# RadioCommunication.net
KiCad netlist of a schematic drawn in Altium Designer
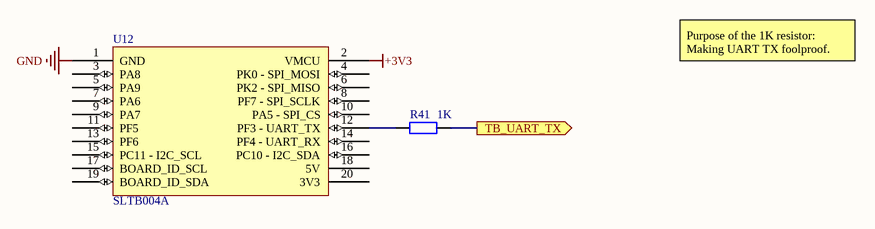
[diagram p0: RadioCommunication.SchDoc]

(export (version "E")
  (design (tool "Eeschema 10.0.6"))
  (components
    (comp (ref "R41")
      (value "1K")
      (footprint "FP_0805_RES")
      (description "Resistor")
      (fields (field (name "TOLERANCE") "5%") (field (name "POWER") "0.125W"))
      (libsource (lib "LKBulls2023") (part "RES"))
    )
    (comp (ref "U12")
      (value "SLTB004A")
      (footprint "SLTB004A")
      (description "SiLabs Thunderboard Sense 2 module")
      (libsource (lib "LKBulls2023") (part "SLTB004A"))
    )
  )
  (nets
    (net (code "1") (name "+3V3") (class "Default")
      (node (ref "U12") (pin "2") (pinfunction "VMCU_2") (pintype "power_in"))
    )
    (net (code "2") (name "/TB_UART_TX") (class "Default")
      (node (ref "R41") (pin "2") (pinfunction "2_2") (pintype "passive"))
    )
    (net (code "3") (name "GND") (class "Default")
      (node (ref "U12") (pin "1") (pinfunction "GND_1") (pintype "power_in"))
    )
    (net (code "4") (name "Net-(U12-PF3_-_UART_TX)") (class "Default")
      (node (ref "R41") (pin "1") (pinfunction "1_1") (pintype "passive"))
      (node (ref "U12") (pin "12") (pinfunction "PF3_-_UART_TX_12") (pintype "bidirectional"))
    )
    (net (code "5") (name "unconnected-(U12-3V3-Pad20)") (class "Default")
      (node (ref "U12") (pin "20") (pinfunction "3V3_20") (pintype "power_in"))
    )
    (net (code "6") (name "unconnected-(U12-5V-Pad18)") (class "Default")
      (node (ref "U12") (pin "18") (pinfunction "5V_18") (pintype "power_in"))
    )
    (net (code "7") (name "unconnected-(U12-BOARD_ID_SCL-Pad17)") (class "Default")
      (node (ref "U12") (pin "17") (pinfunction "BOARD_ID_SCL_17") (pintype "bidirectional"))
    )
    (net (code "8") (name "unconnected-(U12-BOARD_ID_SDA-Pad19)") (class "Default")
      (node (ref "U12") (pin "19") (pinfunction "BOARD_ID_SDA_19") (pintype "bidirectional"))
    )
    (net (code "9") (name "unconnected-(U12-PA5_-_SPI_CS-Pad10)") (class "Default")
      (node (ref "U12") (pin "10") (pinfunction "PA5_-_SPI_CS_10") (pintype "bidirectional"))
    )
    (net (code "10") (name "unconnected-(U12-PA6-Pad7)") (class "Default")
      (node (ref "U12") (pin "7") (pinfunction "PA6_7") (pintype "bidirectional"))
    )
    (net (code "11") (name "unconnected-(U12-PA7-Pad9)") (class "Default")
      (node (ref "U12") (pin "9") (pinfunction "PA7_9") (pintype "bidirectional"))
    )
    (net (code "12") (name "unconnected-(U12-PA8-Pad3)") (class "Default")
      (node (ref "U12") (pin "3") (pinfunction "PA8_3") (pintype "bidirectional"))
    )
    (net (code "13") (name "unconnected-(U12-PA9-Pad5)") (class "Default")
      (node (ref "U12") (pin "5") (pinfunction "PA9_5") (pintype "bidirectional"))
    )
    (net (code "14") (name "unconnected-(U12-PC10_-_I2C_SDA-Pad16)") (class "Default")
      (node (ref "U12") (pin "16") (pinfunction "PC10_-_I2C_SDA_16") (pintype "bidirectional"))
    )
    (net (code "15") (name "unconnected-(U12-PC11_-_I2C_SCL-Pad15)") (class "Default")
      (node (ref "U12") (pin "15") (pinfunction "PC11_-_I2C_SCL_15") (pintype "bidirectional"))
    )
    (net (code "16") (name "unconnected-(U12-PF4_-_UART_RX-Pad14)") (class "Default")
      (node (ref "U12") (pin "14") (pinfunction "PF4_-_UART_RX_14") (pintype "bidirectional"))
    )
    (net (code "17") (name "unconnected-(U12-PF5-Pad11)") (class "Default")
      (node (ref "U12") (pin "11") (pinfunction "PF5_11") (pintype "bidirectional"))
    )
    (net (code "18") (name "unconnected-(U12-PF6-Pad13)") (class "Default")
      (node (ref "U12") (pin "13") (pinfunction "PF6_13") (pintype "bidirectional"))
    )
    (net (code "19") (name "unconnected-(U12-PF7_-_SPI_SCLK-Pad8)") (class "Default")
      (node (ref "U12") (pin "8") (pinfunction "PF7_-_SPI_SCLK_8") (pintype "bidirectional"))
    )
    (net (code "20") (name "unconnected-(U12-PK0_-_SPI_MOSI-Pad4)") (class "Default")
      (node (ref "U12") (pin "4") (pinfunction "PK0_-_SPI_MOSI_4") (pintype "bidirectional"))
    )
    (net (code "21") (name "unconnected-(U12-PK2_-_SPI_MISO-Pad6)") (class "Default")
      (node (ref "U12") (pin "6") (pinfunction "PK2_-_SPI_MISO_6") (pintype "bidirectional"))
    )
  )
)
